# untitled.net
KiCad netlist of a schematic drawn in EAGLE
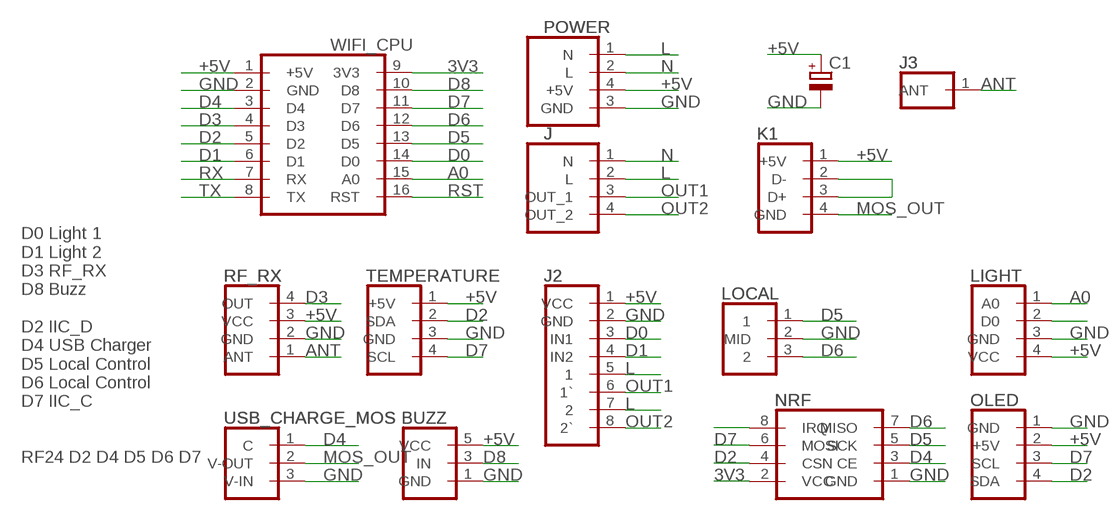
[diagram p0: schematic, sheet 1]

(export (version "E")
  (design (tool "Eeschema 10.0.6"))
  (components
    (comp (ref "BUZZ")
      (value "BUZZ_MODULE")
      (footprint "eagle-import:BUZZ_MODULE")
      (libsource (lib "eagle-import") (part "BUZZ_MODULE"))
    )
    (comp (ref "C1")
      (value "CPOL-EUE5-5")
      (footprint "eagle-import:E5-5")
      (libsource (lib "eagle-import") (part "CPOL-EUE5-5"))
    )
    (comp (ref "J")
      (value "OUT_HEAD_4_AC_2CH")
      (footprint "eagle-import:OUT_HEAD_4_AC_2CH")
      (libsource (lib "eagle-import") (part "OUT_HEAD_4_AC_2CH"))
    )
    (comp (ref "J2")
      (value "2_SOLID_RELAY")
      (footprint "eagle-import:2_SOLID_RELAY")
      (libsource (lib "eagle-import") (part "2_SOLID_RELAY"))
    )
    (comp (ref "J3")
      (value "ANT_315")
      (footprint "eagle-import:ANT_315")
      (libsource (lib "eagle-import") (part "ANT_315"))
    )
    (comp (ref "K1")
      (value "USB_OUTUSB_V")
      (footprint "eagle-import:USB_V_OUT")
      (libsource (lib "eagle-import") (part "USB_OUTUSB_V"))
    )
    (comp (ref "LIGHT")
      (value "LIGHT_DEC")
      (footprint "eagle-import:LIGHT_DEC")
      (libsource (lib "eagle-import") (part "LIGHT_DEC"))
    )
    (comp (ref "LOCAL")
      (value "SELECT_3")
      (footprint "eagle-import:SELECT_3")
      (libsource (lib "eagle-import") (part "SELECT_3"))
    )
    (comp (ref "NRF")
      (value "NRF24L01_MODULE")
      (footprint "eagle-import:NRF24L01")
      (libsource (lib "eagle-import") (part "NRF24L01_MODULE"))
    )
    (comp (ref "OLED")
      (value "IIC_OLED")
      (footprint "eagle-import:IIC_OLED")
      (libsource (lib "eagle-import") (part "IIC_OLED"))
    )
    (comp (ref "POWER")
      (value "AC_DC5V2A")
      (footprint "eagle-import:AC_DC_5V2A")
      (libsource (lib "eagle-import") (part "AC_DC5V2A"))
    )
    (comp (ref "RF_RX")
      (value "315MHZ_RX_SMT")
      (footprint "eagle-import:315MHZ_RX_SMT")
      (libsource (lib "eagle-import") (part "315MHZ_RX_SMT"))
    )
    (comp (ref "TEMPERATURE")
      (value "IIC_TEMPERATURE")
      (footprint "eagle-import:IIC_TEMPERATURE")
      (libsource (lib "eagle-import") (part "IIC_TEMPERATURE"))
    )
    (comp (ref "USB_CHARGE_MOS")
      (value "MOS_IRF520")
      (footprint "eagle-import:MOS_IRF520")
      (libsource (lib "eagle-import") (part "MOS_IRF520"))
    )
    (comp (ref "WIFI_CPU")
      (value "ESP8266_MINI")
      (footprint "eagle-import:ESP8266_MINI")
      (libsource (lib "eagle-import") (part "ESP8266_MINI"))
    )
  )
  (nets
    (net (code "1") (name "/+5V") (class "Default")
      (node (ref "BUZZ") (pin "5") (pinfunction "VCC_5") (pintype "bidirectional"))
      (node (ref "C1") (pin "+") (pinfunction "+_+") (pintype "passive"))
      (node (ref "J2") (pin "1") (pinfunction "VCC_1") (pintype "bidirectional"))
      (node (ref "K1") (pin "1") (pinfunction "+5V_1") (pintype "bidirectional"))
      (node (ref "LIGHT") (pin "4") (pinfunction "VCC_4") (pintype "bidirectional"))
      (node (ref "OLED") (pin "2") (pinfunction "+5V_2") (pintype "bidirectional"))
      (node (ref "POWER") (pin "4") (pinfunction "+5V_4") (pintype "bidirectional"))
      (node (ref "RF_RX") (pin "3") (pinfunction "VCC_3") (pintype "bidirectional"))
      (node (ref "TEMPERATURE") (pin "1") (pinfunction "+5V_1") (pintype "bidirectional"))
      (node (ref "WIFI_CPU") (pin "1") (pinfunction "+5V_1") (pintype "bidirectional"))
    )
    (net (code "2") (name "/3V3") (class "Default")
      (node (ref "NRF") (pin "2") (pinfunction "VCC_2") (pintype "bidirectional"))
      (node (ref "WIFI_CPU") (pin "9") (pinfunction "3V3_9") (pintype "bidirectional"))
    )
    (net (code "3") (name "/A0") (class "Default")
      (node (ref "LIGHT") (pin "1") (pinfunction "A0_1") (pintype "bidirectional"))
      (node (ref "WIFI_CPU") (pin "15") (pinfunction "A0_15") (pintype "bidirectional"))
    )
    (net (code "4") (name "/ANT") (class "Default")
      (node (ref "J3") (pin "1") (pinfunction "ANT_1") (pintype "bidirectional"))
      (node (ref "RF_RX") (pin "1") (pinfunction "ANT_1") (pintype "bidirectional"))
    )
    (net (code "5") (name "/D0") (class "Default")
      (node (ref "J2") (pin "3") (pinfunction "IN1_3") (pintype "bidirectional"))
      (node (ref "WIFI_CPU") (pin "14") (pinfunction "D0_14") (pintype "bidirectional"))
    )
    (net (code "6") (name "/D1") (class "Default")
      (node (ref "J2") (pin "4") (pinfunction "IN2_4") (pintype "bidirectional"))
      (node (ref "WIFI_CPU") (pin "6") (pinfunction "D1_6") (pintype "bidirectional"))
    )
    (net (code "7") (name "/D2") (class "Default")
      (node (ref "NRF") (pin "4") (pinfunction "CSN_4") (pintype "bidirectional"))
      (node (ref "OLED") (pin "4") (pinfunction "SDA_4") (pintype "bidirectional"))
      (node (ref "TEMPERATURE") (pin "2") (pinfunction "SDA_2") (pintype "bidirectional"))
      (node (ref "WIFI_CPU") (pin "5") (pinfunction "D2_5") (pintype "bidirectional"))
    )
    (net (code "8") (name "/D3") (class "Default")
      (node (ref "RF_RX") (pin "4") (pinfunction "OUT_4") (pintype "bidirectional"))
      (node (ref "WIFI_CPU") (pin "4") (pinfunction "D3_4") (pintype "bidirectional"))
    )
    (net (code "9") (name "/D4") (class "Default")
      (node (ref "NRF") (pin "3") (pinfunction "CE_3") (pintype "bidirectional"))
      (node (ref "USB_CHARGE_MOS") (pin "1") (pinfunction "C_1") (pintype "bidirectional"))
      (node (ref "WIFI_CPU") (pin "3") (pinfunction "D4_3") (pintype "bidirectional"))
    )
    (net (code "10") (name "/D5") (class "Default")
      (node (ref "LOCAL") (pin "1") (pinfunction "1_1") (pintype "bidirectional"))
      (node (ref "NRF") (pin "5") (pinfunction "SCK_5") (pintype "bidirectional"))
      (node (ref "WIFI_CPU") (pin "13") (pinfunction "D5_13") (pintype "bidirectional"))
    )
    (net (code "11") (name "/D6") (class "Default")
      (node (ref "LOCAL") (pin "3") (pinfunction "2_3") (pintype "bidirectional"))
      (node (ref "NRF") (pin "7") (pinfunction "MISO_7") (pintype "bidirectional"))
      (node (ref "WIFI_CPU") (pin "12") (pinfunction "D6_12") (pintype "bidirectional"))
    )
    (net (code "12") (name "/D7") (class "Default")
      (node (ref "NRF") (pin "6") (pinfunction "MOSI_6") (pintype "bidirectional"))
      (node (ref "OLED") (pin "3") (pinfunction "SCL_3") (pintype "bidirectional"))
      (node (ref "TEMPERATURE") (pin "4") (pinfunction "SCL_4") (pintype "bidirectional"))
      (node (ref "WIFI_CPU") (pin "11") (pinfunction "D7_11") (pintype "bidirectional"))
    )
    (net (code "13") (name "/D8") (class "Default")
      (node (ref "BUZZ") (pin "3") (pinfunction "IN_3") (pintype "bidirectional"))
      (node (ref "WIFI_CPU") (pin "10") (pinfunction "D8_10") (pintype "bidirectional"))
    )
    (net (code "14") (name "/GND") (class "Default")
      (node (ref "BUZZ") (pin "1") (pinfunction "GND_1") (pintype "bidirectional"))
      (node (ref "C1") (pin "-") (pinfunction "-_-") (pintype "passive"))
      (node (ref "J2") (pin "2") (pinfunction "GND_2") (pintype "bidirectional"))
      (node (ref "LIGHT") (pin "3") (pinfunction "GND_3") (pintype "bidirectional"))
      (node (ref "LOCAL") (pin "2") (pinfunction "MID_2") (pintype "bidirectional"))
      (node (ref "NRF") (pin "1") (pinfunction "GND_1") (pintype "bidirectional"))
      (node (ref "OLED") (pin "1") (pinfunction "GND_1") (pintype "bidirectional"))
      (node (ref "POWER") (pin "3") (pinfunction "GND_3") (pintype "bidirectional"))
      (node (ref "RF_RX") (pin "2") (pinfunction "GND_2") (pintype "bidirectional"))
      (node (ref "TEMPERATURE") (pin "3") (pinfunction "GND_3") (pintype "bidirectional"))
      (node (ref "USB_CHARGE_MOS") (pin "3") (pinfunction "V-IN_3") (pintype "bidirectional"))
      (node (ref "WIFI_CPU") (pin "2") (pinfunction "GND_2") (pintype "bidirectional"))
    )
    (net (code "15") (name "/L") (class "Default")
      (node (ref "J") (pin "2") (pinfunction "L_2") (pintype "bidirectional"))
      (node (ref "J2") (pin "5") (pinfunction "1_5") (pintype "bidirectional"))
      (node (ref "J2") (pin "7") (pinfunction "2_7") (pintype "bidirectional"))
      (node (ref "POWER") (pin "1") (pinfunction "N_1") (pintype "bidirectional"))
    )
    (net (code "16") (name "/MOS_OUT") (class "Default")
      (node (ref "K1") (pin "4") (pinfunction "GND_4") (pintype "bidirectional"))
      (node (ref "USB_CHARGE_MOS") (pin "2") (pinfunction "V-OUT_2") (pintype "bidirectional"))
    )
    (net (code "17") (name "/N") (class "Default")
      (node (ref "J") (pin "1") (pinfunction "N_1") (pintype "bidirectional"))
      (node (ref "POWER") (pin "2") (pinfunction "L_2") (pintype "bidirectional"))
    )
    (net (code "18") (name "/OUT1") (class "Default")
      (node (ref "J") (pin "3") (pinfunction "OUT_1_3") (pintype "bidirectional"))
      (node (ref "J2") (pin "6") (pinfunction "1`_6") (pintype "bidirectional"))
    )
    (net (code "19") (name "/OUT2") (class "Default")
      (node (ref "J") (pin "4") (pinfunction "OUT_2_4") (pintype "bidirectional"))
      (node (ref "J2") (pin "8") (pinfunction "2`_8") (pintype "bidirectional"))
    )
    (net (code "20") (name "/RST") (class "Default")
      (node (ref "WIFI_CPU") (pin "16") (pinfunction "RST_16") (pintype "bidirectional"))
    )
    (net (code "21") (name "/RX") (class "Default")
      (node (ref "WIFI_CPU") (pin "7") (pinfunction "RX_7") (pintype "bidirectional"))
    )
    (net (code "22") (name "/TX") (class "Default")
      (node (ref "WIFI_CPU") (pin "8") (pinfunction "TX_8") (pintype "bidirectional"))
    )
    (net (code "23") (name "Net-(K1-D+)") (class "Default")
      (node (ref "K1") (pin "2") (pinfunction "D-_2") (pintype "bidirectional"))
      (node (ref "K1") (pin "3") (pinfunction "D+_3") (pintype "bidirectional"))
    )
    (net (code "24") (name "unconnected-(LIGHT-D0-Pad2)") (class "Default")
      (node (ref "LIGHT") (pin "2") (pinfunction "D0_2") (pintype "bidirectional"))
    )
    (net (code "25") (name "unconnected-(NRF-IRQ-Pad8)") (class "Default")
      (node (ref "NRF") (pin "8") (pinfunction "IRQ_8") (pintype "bidirectional"))
    )
  )
)
